# ATTINY44.net
KiCad netlist of a schematic drawn in EAGLE
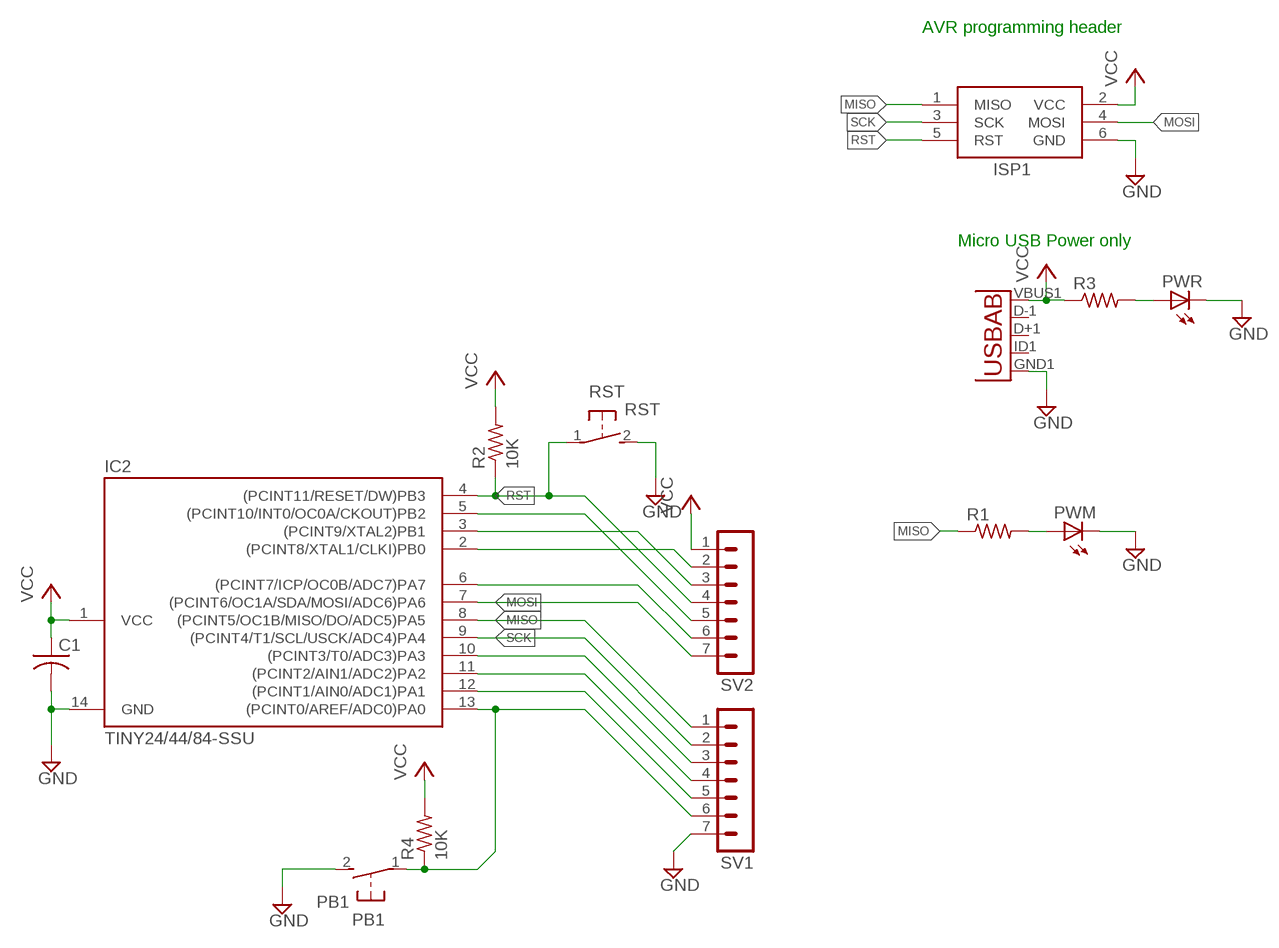
[diagram p0: schematic, sheet 1]

(export (version "E")
  (design (tool "Eeschema 10.0.6"))
  (components
    (comp (ref "C1")
      (value "C-USC0805")
      (footprint "eagle-import:C0805")
      (libsource (lib "eagle-import") (part "C-USC0805"))
    )
    (comp (ref "IC2")
      (value "TINY24/44/84-SSU")
      (footprint "eagle-import:SOIC14")
      (libsource (lib "eagle-import") (part "TINY24/44/84-SSU"))
    )
    (comp (ref "ISP1")
      (value "AVRISP-6")
      (footprint "eagle-import:AVRISP")
      (libsource (lib "eagle-import") (part "AVRISP-6"))
    )
    (comp (ref "PB1")
      (value "PB1")
      (footprint "eagle-import:DTSM-3")
      (libsource (lib "eagle-import") (part "DTSM-3"))
    )
    (comp (ref "PWM")
      (value "LEDCHIPLED_0805")
      (footprint "eagle-import:CHIPLED_0805")
      (libsource (lib "eagle-import") (part "LEDCHIPLED_0805"))
    )
    (comp (ref "PWR")
      (value "LEDCHIPLED_0805")
      (footprint "eagle-import:CHIPLED_0805")
      (libsource (lib "eagle-import") (part "LEDCHIPLED_0805"))
    )
    (comp (ref "R1")
      (value "R-US_R0805")
      (footprint "eagle-import:R0805")
      (libsource (lib "eagle-import") (part "R-US_R0805"))
    )
    (comp (ref "R2")
      (value "10K")
      (footprint "eagle-import:R0805")
      (libsource (lib "eagle-import") (part "R-US_R0805"))
    )
    (comp (ref "R3")
      (value "R-US_R0805")
      (footprint "eagle-import:R0805")
      (libsource (lib "eagle-import") (part "R-US_R0805"))
    )
    (comp (ref "R4")
      (value "10K")
      (footprint "eagle-import:R0805")
      (libsource (lib "eagle-import") (part "R-US_R0805"))
    )
    (comp (ref "RST")
      (value "RST")
      (footprint "eagle-import:DTSM-3")
      (libsource (lib "eagle-import") (part "DTSM-3"))
    )
    (comp (ref "SV1")
      (value "MA07-1")
      (footprint "eagle-import:MA07-1")
      (libsource (lib "eagle-import") (part "MA07-1"))
    )
    (comp (ref "SV2")
      (value "MA07-1")
      (footprint "eagle-import:MA07-1")
      (libsource (lib "eagle-import") (part "MA07-1"))
    )
    (comp (ref "U1")
      (value "USB\"\"")
      (footprint "eagle-import:USB-MICRO-SMD")
      (libsource (lib "eagle-import") (part "USB{dblquote}{dblquote}"))
    )
  )
  (nets
    (net (code "1") (name "GND") (class "Default")
      (node (ref "C1") (pin "2") (pinfunction "2_2") (pintype "passive"))
      (node (ref "IC2") (pin "14") (pinfunction "GND_14") (pintype "power_in"))
      (node (ref "ISP1") (pin "6") (pinfunction "GND_6") (pintype "power_in"))
      (node (ref "PB1") (pin "2") (pinfunction "2_2") (pintype "passive"))
      (node (ref "PWM") (pin "C") (pinfunction "C_C") (pintype "passive"))
      (node (ref "PWR") (pin "C") (pinfunction "C_C") (pintype "passive"))
      (node (ref "RST") (pin "2") (pinfunction "2_2") (pintype "passive"))
      (node (ref "SV1") (pin "7") (pinfunction "7_7") (pintype "passive"))
      (node (ref "U1") (pin "GND1") (pinfunction "GND_GND1") (pintype "bidirectional"))
    )
    (net (code "2") (name "MISO") (class "Default")
      (node (ref "IC2") (pin "8") (pinfunction "(PCINT5/OC1B/MISO/DO/ADC5)PA5_8") (pintype "bidirectional"))
      (node (ref "ISP1") (pin "1") (pinfunction "MISO_1") (pintype "input"))
      (node (ref "R1") (pin "1") (pinfunction "1_1") (pintype "passive"))
      (node (ref "SV1") (pin "1") (pinfunction "1_1") (pintype "passive"))
    )
    (net (code "3") (name "MOSI") (class "Default")
      (node (ref "IC2") (pin "7") (pinfunction "(PCINT6/OC1A/SDA/MOSI/ADC6)PA6_7") (pintype "bidirectional"))
      (node (ref "ISP1") (pin "4") (pinfunction "MOSI_4") (pintype "output"))
      (node (ref "SV2") (pin "7") (pinfunction "7_7") (pintype "passive"))
    )
    (net (code "4") (name "Net-(IC2-(PCINT0{slash}AREF{slash}ADC0)PA0)") (class "Default")
      (node (ref "IC2") (pin "13") (pinfunction "(PCINT0/AREF/ADC0)PA0_13") (pintype "bidirectional"))
      (node (ref "PB1") (pin "1") (pinfunction "1_1") (pintype "passive"))
      (node (ref "R4") (pin "1") (pinfunction "1_1") (pintype "passive"))
      (node (ref "SV1") (pin "6") (pinfunction "6_6") (pintype "passive"))
    )
    (net (code "5") (name "Net-(IC2-(PCINT1{slash}AIN0{slash}ADC1)PA1)") (class "Default")
      (node (ref "IC2") (pin "12") (pinfunction "(PCINT1/AIN0/ADC1)PA1_12") (pintype "bidirectional"))
      (node (ref "SV1") (pin "5") (pinfunction "5_5") (pintype "passive"))
    )
    (net (code "6") (name "Net-(IC2-(PCINT2{slash}AIN1{slash}ADC2)PA2)") (class "Default")
      (node (ref "IC2") (pin "11") (pinfunction "(PCINT2/AIN1/ADC2)PA2_11") (pintype "bidirectional"))
      (node (ref "SV1") (pin "4") (pinfunction "4_4") (pintype "passive"))
    )
    (net (code "7") (name "Net-(IC2-(PCINT3{slash}T0{slash}ADC3)PA3)") (class "Default")
      (node (ref "IC2") (pin "10") (pinfunction "(PCINT3/T0/ADC3)PA3_10") (pintype "bidirectional"))
      (node (ref "SV1") (pin "3") (pinfunction "3_3") (pintype "passive"))
    )
    (net (code "8") (name "Net-(IC2-(PCINT7{slash}ICP{slash}OC0B{slash}ADC7)PA7)") (class "Default")
      (node (ref "IC2") (pin "6") (pinfunction "(PCINT7/ICP/OC0B/ADC7)PA7_6") (pintype "bidirectional"))
      (node (ref "SV2") (pin "6") (pinfunction "6_6") (pintype "passive"))
    )
    (net (code "9") (name "Net-(IC2-(PCINT8{slash}XTAL1{slash}CLKI)PB0)") (class "Default")
      (node (ref "IC2") (pin "2") (pinfunction "(PCINT8/XTAL1/CLKI)PB0_2") (pintype "bidirectional"))
      (node (ref "SV2") (pin "2") (pinfunction "2_2") (pintype "passive"))
    )
    (net (code "10") (name "Net-(IC2-(PCINT9{slash}XTAL2)PB1)") (class "Default")
      (node (ref "IC2") (pin "3") (pinfunction "(PCINT9/XTAL2)PB1_3") (pintype "bidirectional"))
      (node (ref "SV2") (pin "3") (pinfunction "3_3") (pintype "passive"))
    )
    (net (code "11") (name "Net-(IC2-(PCINT10{slash}INT0{slash}OC0A{slash}CKOUT)PB2)") (class "Default")
      (node (ref "IC2") (pin "5") (pinfunction "(PCINT10/INT0/OC0A/CKOUT)PB2_5") (pintype "bidirectional"))
      (node (ref "SV2") (pin "5") (pinfunction "5_5") (pintype "passive"))
    )
    (net (code "12") (name "Net-(PWM-PadA)") (class "Default")
      (node (ref "PWM") (pin "A") (pinfunction "A_A") (pintype "passive"))
      (node (ref "R1") (pin "2") (pinfunction "2_2") (pintype "passive"))
    )
    (net (code "13") (name "Net-(PWR-PadA)") (class "Default")
      (node (ref "PWR") (pin "A") (pinfunction "A_A") (pintype "passive"))
      (node (ref "R3") (pin "2") (pinfunction "2_2") (pintype "passive"))
    )
    (net (code "14") (name "RST") (class "Default")
      (node (ref "IC2") (pin "4") (pinfunction "(PCINT11/RESET/DW)PB3_4") (pintype "bidirectional"))
      (node (ref "ISP1") (pin "5") (pinfunction "RST_5") (pintype "output"))
      (node (ref "R2") (pin "1") (pinfunction "1_1") (pintype "passive"))
      (node (ref "RST") (pin "1") (pinfunction "1_1") (pintype "passive"))
      (node (ref "SV2") (pin "4") (pinfunction "4_4") (pintype "passive"))
    )
    (net (code "15") (name "SCK") (class "Default")
      (node (ref "IC2") (pin "9") (pinfunction "(PCINT4/T1/SCL/USCK/ADC4)PA4_9") (pintype "bidirectional"))
      (node (ref "ISP1") (pin "3") (pinfunction "SCK_3") (pintype "output"))
      (node (ref "SV1") (pin "2") (pinfunction "2_2") (pintype "passive"))
    )
    (net (code "16") (name "VCC") (class "Default")
      (node (ref "C1") (pin "1") (pinfunction "1_1") (pintype "passive"))
      (node (ref "IC2") (pin "1") (pinfunction "VCC_1") (pintype "power_in"))
      (node (ref "ISP1") (pin "2") (pinfunction "VCC_2") (pintype "power_in"))
      (node (ref "R2") (pin "2") (pinfunction "2_2") (pintype "passive"))
      (node (ref "R3") (pin "1") (pinfunction "1_1") (pintype "passive"))
      (node (ref "R4") (pin "2") (pinfunction "2_2") (pintype "passive"))
      (node (ref "SV2") (pin "1") (pinfunction "1_1") (pintype "passive"))
      (node (ref "U1") (pin "VBUS1") (pinfunction "VBUS_VBUS1") (pintype "bidirectional"))
    )
    (net (code "17") (name "unconnected-(U1-D+-PadD+1)") (class "Default")
      (node (ref "U1") (pin "D+1") (pinfunction "D+_D+1") (pintype "bidirectional"))
    )
    (net (code "18") (name "unconnected-(U1-D--PadD-1)") (class "Default")
      (node (ref "U1") (pin "D-1") (pinfunction "D-_D-1") (pintype "bidirectional"))
    )
    (net (code "19") (name "unconnected-(U1-USBID-PadID1)") (class "Default")
      (node (ref "U1") (pin "ID1") (pinfunction "USBID_ID1") (pintype "bidirectional"))
    )
  )
)
